# HYDRA_V3_NAV.net
KiCad netlist of a schematic drawn in Altium Designer
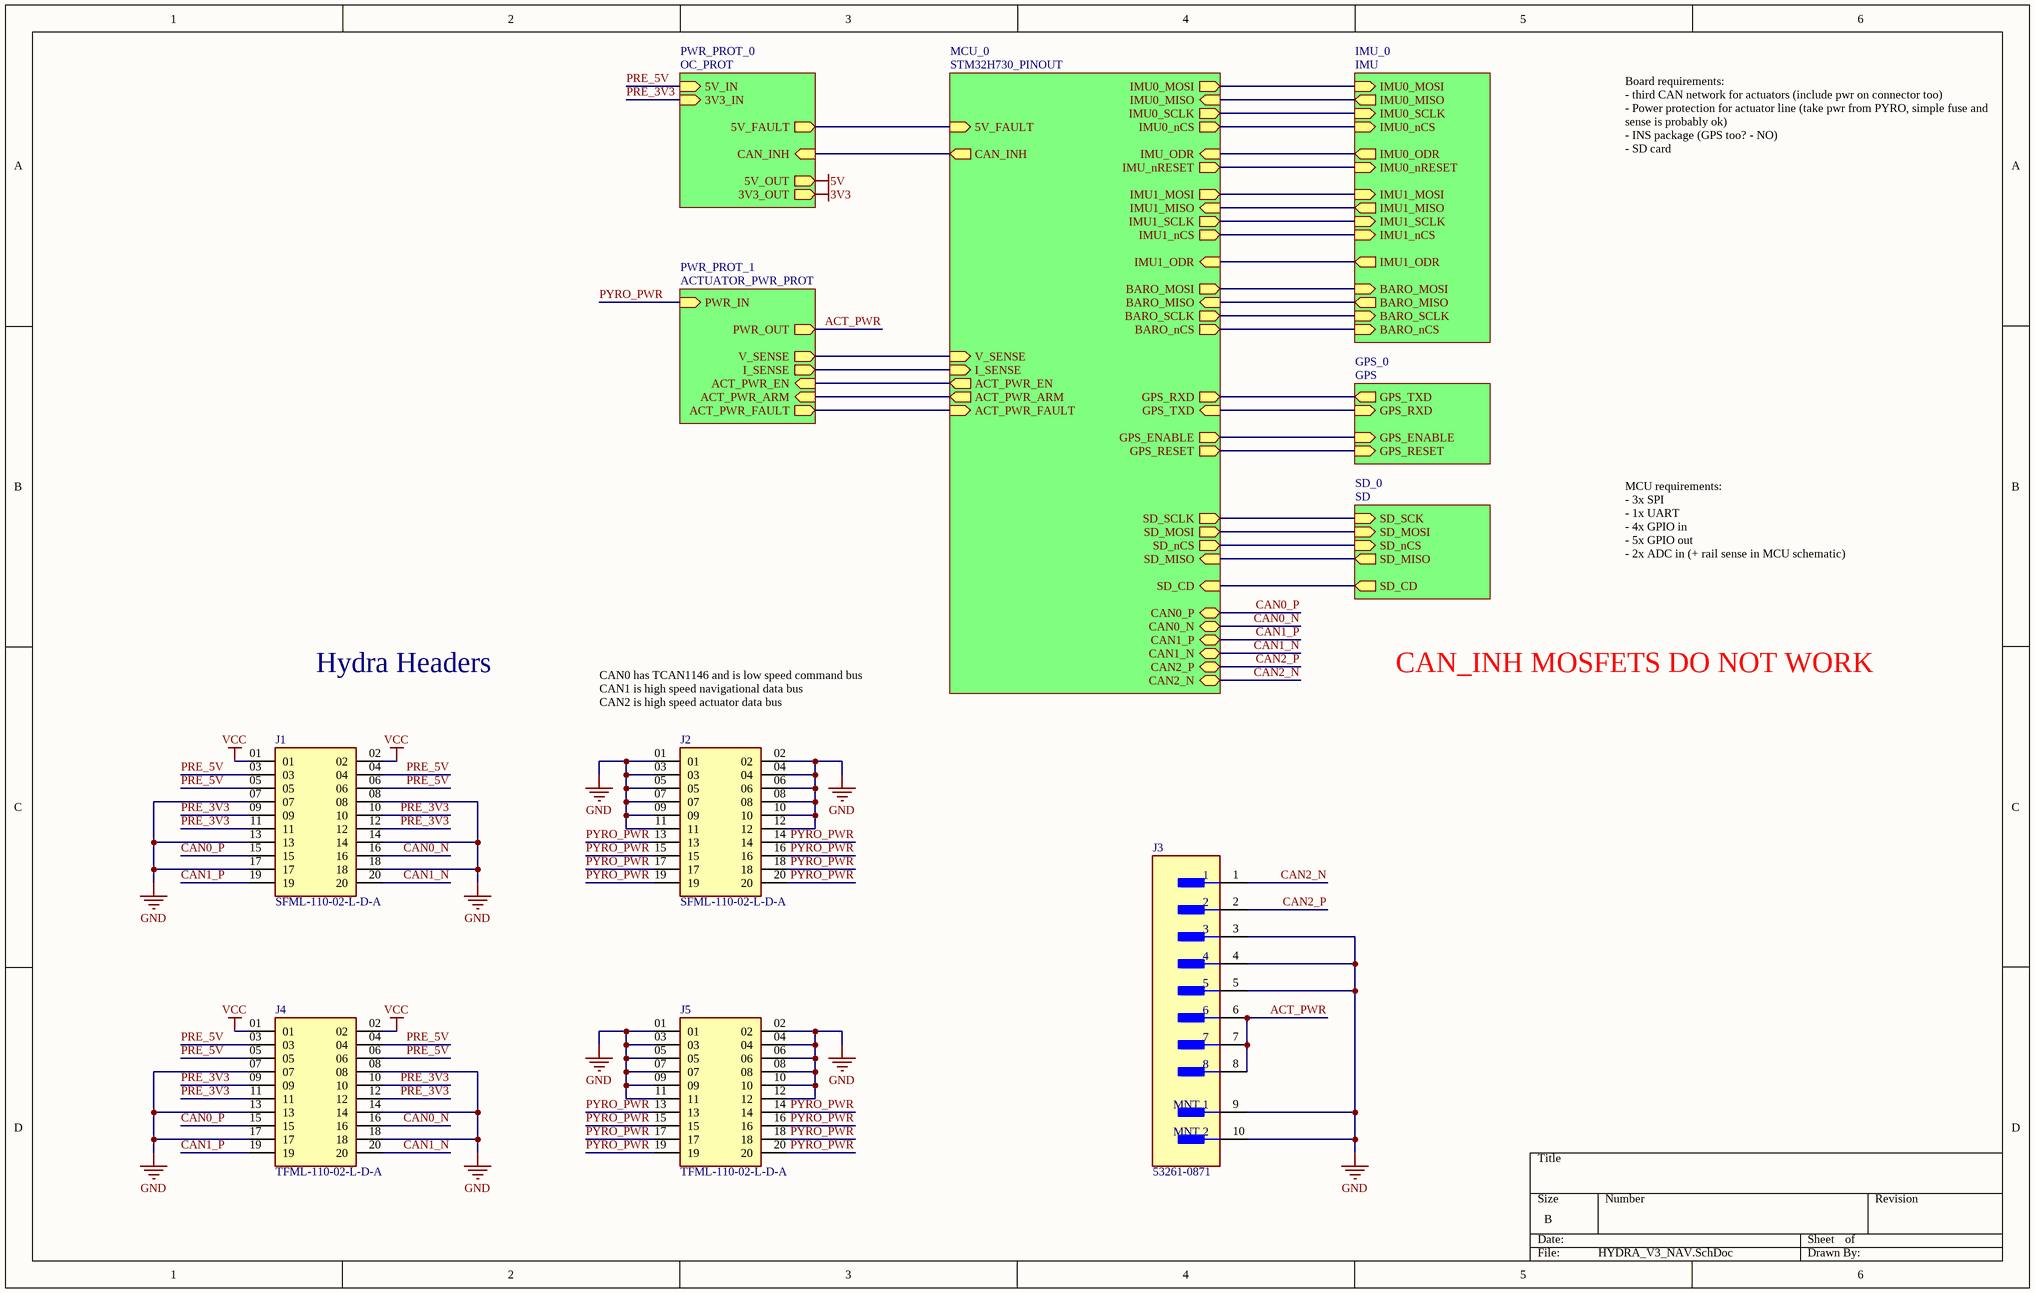
[diagram p0: HYDRA_V3_NAV.SchDoc]

(export (version "E")
  (design (tool "Eeschema 10.0.6"))
  (components
    (comp (ref "J1")
      (value "SFML-110-02-L-D-A")
      (footprint "SFML-110-02-L-D-A-Footprint-1")
      (libsource (lib "Space Concordia") (part "SFML-110-02-L-D-A"))
    )
    (comp (ref "J2")
      (value "SFML-110-02-L-D-A")
      (footprint "SFML-110-02-L-D-A-Footprint-1")
      (libsource (lib "Space Concordia") (part "SFML-110-02-L-D-A"))
    )
    (comp (ref "J3")
      (value "53261-0871")
      (footprint "FP-532610871-MFG")
      (libsource (lib "Space Concordia") (part "98b5586d6b3804e276fbd0410cd4945"))
    )
    (comp (ref "J4")
      (value "TFML-110-02-L-D-A")
      (footprint "TFML-110-02-L-D-A-Footprint-1")
      (description "Board Connector, 20 Contact(s), 2 Row(s), Male, Straight, Surface Mount Terminal")
      (libsource (lib "Space Concordia") (part "TFML-110-02-L-D-A"))
    )
    (comp (ref "J5")
      (value "TFML-110-02-L-D-A")
      (footprint "TFML-110-02-L-D-A-Footprint-1")
      (description "Board Connector, 20 Contact(s), 2 Row(s), Male, Straight, Surface Mount Terminal")
      (libsource (lib "Space Concordia") (part "TFML-110-02-L-D-A"))
    )
  )
  (nets
    (net (code "2") (name "/ACT_PWR") (class "Default")
      (node (ref "J3") (pin "6") (pinfunction "6_6") (pintype "passive"))
      (node (ref "J3") (pin "7") (pinfunction "7_7") (pintype "passive"))
      (node (ref "J3") (pin "8") (pinfunction "8_8") (pintype "passive"))
    )
    (net (code "10") (name "/CAN0_N") (class "Default")
      (node (ref "J1") (pin "16") (pinfunction "16_16") (pintype "passive"))
      (node (ref "J4") (pin "16") (pinfunction "16_16") (pintype "passive"))
    )
    (net (code "11") (name "/CAN0_P") (class "Default")
      (node (ref "J1") (pin "15") (pinfunction "15_15") (pintype "passive"))
      (node (ref "J4") (pin "15") (pinfunction "15_15") (pintype "passive"))
    )
    (net (code "12") (name "/CAN1_N") (class "Default")
      (node (ref "J1") (pin "20") (pinfunction "20_20") (pintype "passive"))
      (node (ref "J4") (pin "20") (pinfunction "20_20") (pintype "passive"))
    )
    (net (code "13") (name "/CAN1_P") (class "Default")
      (node (ref "J1") (pin "19") (pinfunction "19_19") (pintype "passive"))
      (node (ref "J4") (pin "19") (pinfunction "19_19") (pintype "passive"))
    )
    (net (code "14") (name "/CAN2_N") (class "Default")
      (node (ref "J3") (pin "1") (pinfunction "1_1") (pintype "passive"))
    )
    (net (code "15") (name "/CAN2_P") (class "Default")
      (node (ref "J3") (pin "2") (pinfunction "2_2") (pintype "passive"))
    )
    (net (code "33") (name "/PRE_3V3") (class "Default")
      (node (ref "J1") (pin "09") (pinfunction "09_09") (pintype "passive"))
      (node (ref "J1") (pin "10") (pinfunction "10_10") (pintype "passive"))
      (node (ref "J1") (pin "11") (pinfunction "11_11") (pintype "passive"))
      (node (ref "J1") (pin "12") (pinfunction "12_12") (pintype "passive"))
      (node (ref "J4") (pin "09") (pinfunction "09_09") (pintype "passive"))
      (node (ref "J4") (pin "10") (pinfunction "10_10") (pintype "passive"))
      (node (ref "J4") (pin "11") (pinfunction "11_11") (pintype "passive"))
      (node (ref "J4") (pin "12") (pinfunction "12_12") (pintype "passive"))
    )
    (net (code "34") (name "/PRE_5V") (class "Default")
      (node (ref "J1") (pin "03") (pinfunction "03_03") (pintype "passive"))
      (node (ref "J1") (pin "04") (pinfunction "04_04") (pintype "passive"))
      (node (ref "J1") (pin "05") (pinfunction "05_05") (pintype "passive"))
      (node (ref "J1") (pin "06") (pinfunction "06_06") (pintype "passive"))
      (node (ref "J4") (pin "03") (pinfunction "03_03") (pintype "passive"))
      (node (ref "J4") (pin "04") (pinfunction "04_04") (pintype "passive"))
      (node (ref "J4") (pin "05") (pinfunction "05_05") (pintype "passive"))
      (node (ref "J4") (pin "06") (pinfunction "06_06") (pintype "passive"))
    )
    (net (code "35") (name "/PYRO_PWR") (class "Default")
      (node (ref "J2") (pin "13") (pinfunction "13_13") (pintype "passive"))
      (node (ref "J2") (pin "14") (pinfunction "14_14") (pintype "passive"))
      (node (ref "J2") (pin "15") (pinfunction "15_15") (pintype "passive"))
      (node (ref "J2") (pin "16") (pinfunction "16_16") (pintype "passive"))
      (node (ref "J2") (pin "17") (pinfunction "17_17") (pintype "passive"))
      (node (ref "J2") (pin "18") (pinfunction "18_18") (pintype "passive"))
      (node (ref "J2") (pin "19") (pinfunction "19_19") (pintype "passive"))
      (node (ref "J2") (pin "20") (pinfunction "20_20") (pintype "passive"))
      (node (ref "J5") (pin "13") (pinfunction "13_13") (pintype "passive"))
      (node (ref "J5") (pin "14") (pinfunction "14_14") (pintype "passive"))
      (node (ref "J5") (pin "15") (pinfunction "15_15") (pintype "passive"))
      (node (ref "J5") (pin "16") (pinfunction "16_16") (pintype "passive"))
      (node (ref "J5") (pin "17") (pinfunction "17_17") (pintype "passive"))
      (node (ref "J5") (pin "18") (pinfunction "18_18") (pintype "passive"))
      (node (ref "J5") (pin "19") (pinfunction "19_19") (pintype "passive"))
      (node (ref "J5") (pin "20") (pinfunction "20_20") (pintype "passive"))
    )
    (net (code "44") (name "GND") (class "Default")
      (node (ref "J1") (pin "07") (pinfunction "07_07") (pintype "passive"))
      (node (ref "J1") (pin "08") (pinfunction "08_08") (pintype "passive"))
      (node (ref "J1") (pin "13") (pinfunction "13_13") (pintype "passive"))
      (node (ref "J1") (pin "14") (pinfunction "14_14") (pintype "passive"))
      (node (ref "J1") (pin "17") (pinfunction "17_17") (pintype "passive"))
      (node (ref "J1") (pin "18") (pinfunction "18_18") (pintype "passive"))
      (node (ref "J2") (pin "01") (pinfunction "01_01") (pintype "passive"))
      (node (ref "J2") (pin "02") (pinfunction "02_02") (pintype "passive"))
      (node (ref "J2") (pin "03") (pinfunction "03_03") (pintype "passive"))
      (node (ref "J2") (pin "04") (pinfunction "04_04") (pintype "passive"))
      (node (ref "J2") (pin "05") (pinfunction "05_05") (pintype "passive"))
      (node (ref "J2") (pin "06") (pinfunction "06_06") (pintype "passive"))
      (node (ref "J2") (pin "07") (pinfunction "07_07") (pintype "passive"))
      (node (ref "J2") (pin "08") (pinfunction "08_08") (pintype "passive"))
      (node (ref "J2") (pin "09") (pinfunction "09_09") (pintype "passive"))
      (node (ref "J2") (pin "10") (pinfunction "10_10") (pintype "passive"))
      (node (ref "J2") (pin "11") (pinfunction "11_11") (pintype "passive"))
      (node (ref "J2") (pin "12") (pinfunction "12_12") (pintype "passive"))
      (node (ref "J3") (pin "10") (pinfunction "MNT_2_10") (pintype "passive"))
      (node (ref "J3") (pin "3") (pinfunction "3_3") (pintype "passive"))
      (node (ref "J3") (pin "4") (pinfunction "4_4") (pintype "passive"))
      (node (ref "J3") (pin "5") (pinfunction "5_5") (pintype "passive"))
      (node (ref "J3") (pin "9") (pinfunction "MNT_1_9") (pintype "passive"))
      (node (ref "J4") (pin "07") (pinfunction "07_07") (pintype "passive"))
      (node (ref "J4") (pin "08") (pinfunction "08_08") (pintype "passive"))
      (node (ref "J4") (pin "13") (pinfunction "13_13") (pintype "passive"))
      (node (ref "J4") (pin "14") (pinfunction "14_14") (pintype "passive"))
      (node (ref "J4") (pin "17") (pinfunction "17_17") (pintype "passive"))
      (node (ref "J4") (pin "18") (pinfunction "18_18") (pintype "passive"))
      (node (ref "J5") (pin "01") (pinfunction "01_01") (pintype "passive"))
      (node (ref "J5") (pin "02") (pinfunction "02_02") (pintype "passive"))
      (node (ref "J5") (pin "03") (pinfunction "03_03") (pintype "passive"))
      (node (ref "J5") (pin "04") (pinfunction "04_04") (pintype "passive"))
      (node (ref "J5") (pin "05") (pinfunction "05_05") (pintype "passive"))
      (node (ref "J5") (pin "06") (pinfunction "06_06") (pintype "passive"))
      (node (ref "J5") (pin "07") (pinfunction "07_07") (pintype "passive"))
      (node (ref "J5") (pin "08") (pinfunction "08_08") (pintype "passive"))
      (node (ref "J5") (pin "09") (pinfunction "09_09") (pintype "passive"))
      (node (ref "J5") (pin "10") (pinfunction "10_10") (pintype "passive"))
      (node (ref "J5") (pin "11") (pinfunction "11_11") (pintype "passive"))
      (node (ref "J5") (pin "12") (pinfunction "12_12") (pintype "passive"))
    )
    (net (code "45") (name "VCC") (class "Default")
      (node (ref "J1") (pin "01") (pinfunction "01_01") (pintype "passive"))
      (node (ref "J1") (pin "02") (pinfunction "02_02") (pintype "passive"))
      (node (ref "J4") (pin "01") (pinfunction "01_01") (pintype "passive"))
      (node (ref "J4") (pin "02") (pinfunction "02_02") (pintype "passive"))
    )
  )
)
